# SCH_MAX153_interceptor_2023-04-02.net
KiCad netlist of a schematic drawn in EasyEDA
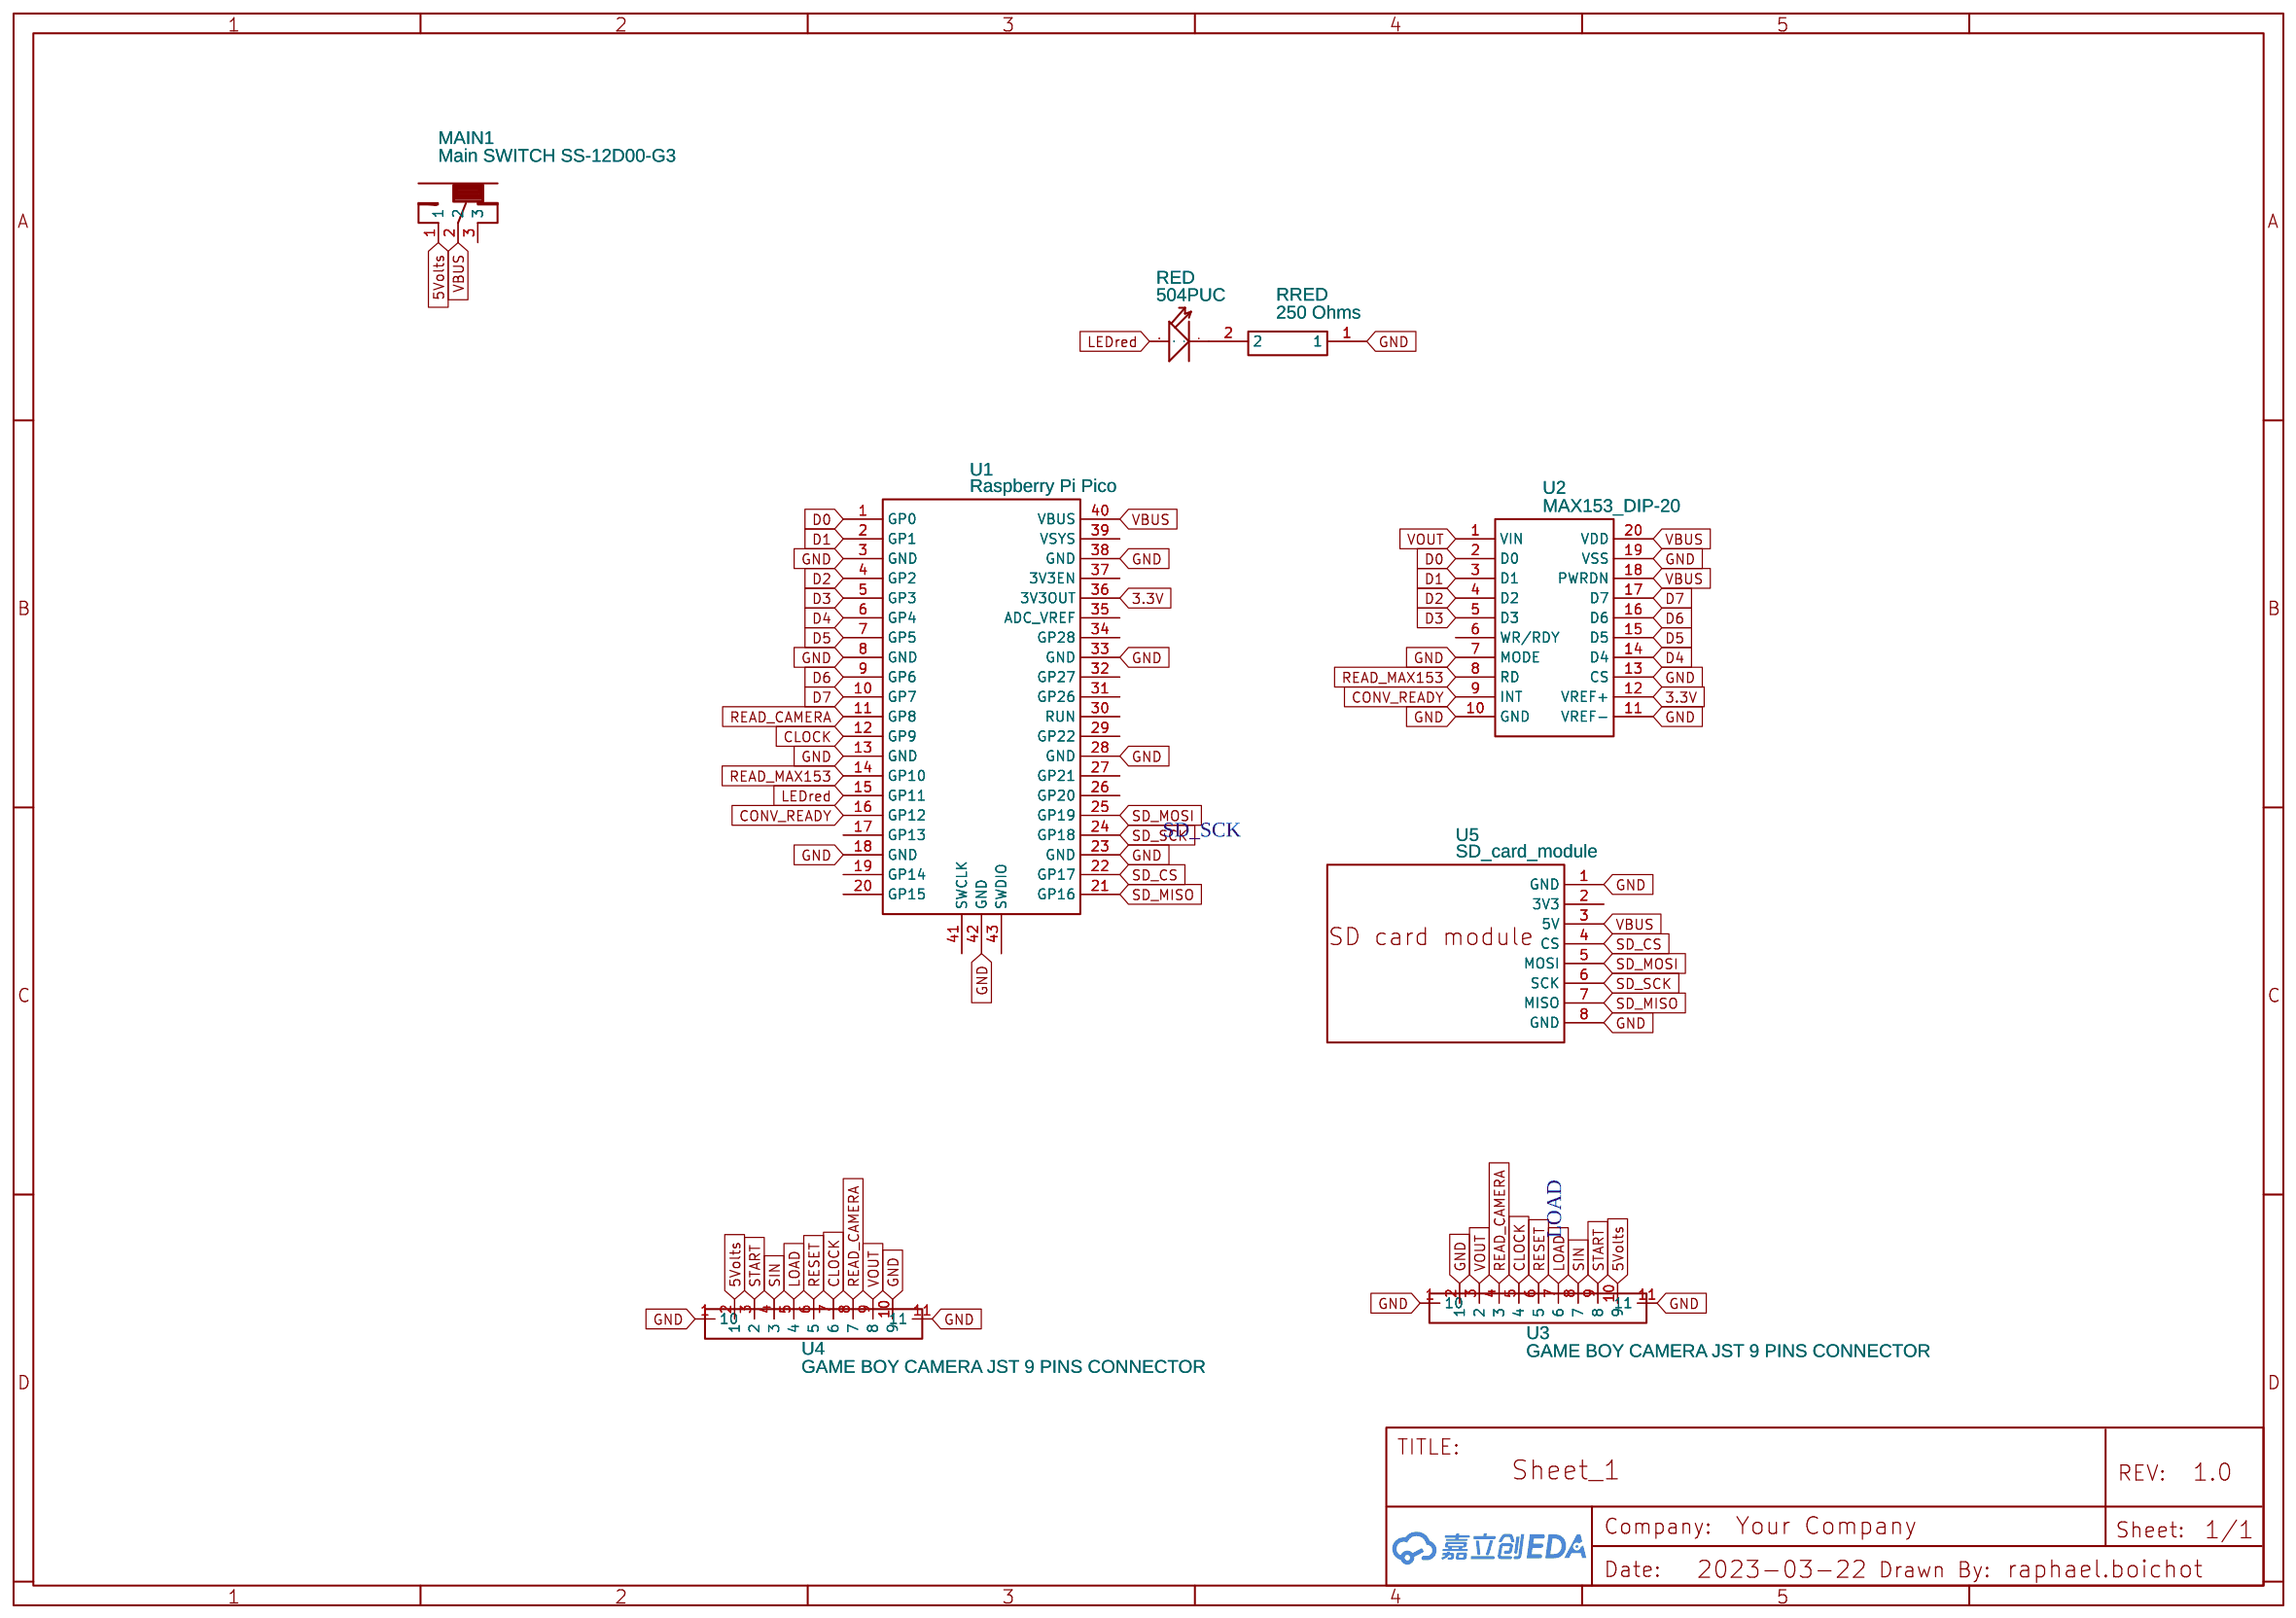
[diagram p0: schematic sheet]

(export (version "E")
  (design (tool "Eeschema 10.0.6"))
  (components
    (comp (ref "MAIN1")
      (value "Main SWITCH SS-12D00-G3")
      (fields (field (name "BOM_Manufacturer Part") "TOGGLE SWITCH SS-12D00-G3"))
      (libsource (lib "") (part "TOGGLE SWITCH SS-12D00-G3"))
    )
    (comp (ref "RED") (value "504PUC") (libsource (lib "") (part "504PUC")))
    (comp (ref "RRED") (value "250 Ohms") (libsource (lib "") (part "RESITOR")))
    (comp (ref "U1") (value "Raspberry Pi Pico") (libsource (lib "") (part "Raspberry Pi Pico")))
    (comp (ref "U2") (value "MAX153_DIP-20") (libsource (lib "") (part "MAX153_DIP-20")))
    (comp (ref "U3")
      (value "GAME BOY CAMERA JST 9 PINS CONNECTOR")
      (libsource (lib "") (part "GAME BOY CAMERA JST 9 PINS CONNECTOR"))
    )
    (comp (ref "U4")
      (value "GAME BOY CAMERA JST 9 PINS CONNECTOR")
      (libsource (lib "") (part "GAME BOY CAMERA JST 9 PINS CONNECTOR_1"))
    )
    (comp (ref "U5") (value "SD_card_module") (libsource (lib "") (part "SD_card_module")))
  )
  (nets
    (net (code "1") (name "3.3V") (class "Default")
      (node (ref "U1") (pin "36") (pinfunction "3V3OUT_36") (pintype "unspecified"))
      (node (ref "U2") (pin "12") (pinfunction "VREF+_12") (pintype "unspecified"))
    )
    (net (code "2") (name "5Volts") (class "Default")
      (node (ref "MAIN1") (pin "1") (pinfunction "1_1") (pintype "bidirectional"))
      (node (ref "U3") (pin "10") (pinfunction "9_10") (pintype "unspecified"))
      (node (ref "U4") (pin "2") (pinfunction "1_2") (pintype "unspecified"))
    )
    (net (code "3") (name "CLOCK") (class "Default")
      (node (ref "U1") (pin "12") (pinfunction "GP9_12") (pintype "unspecified"))
      (node (ref "U3") (pin "5") (pinfunction "4_5") (pintype "unspecified"))
      (node (ref "U4") (pin "7") (pinfunction "6_7") (pintype "unspecified"))
    )
    (net (code "4") (name "CONV_READY") (class "Default")
      (node (ref "U1") (pin "16") (pinfunction "GP12_16") (pintype "unspecified"))
      (node (ref "U2") (pin "9") (pinfunction "INT_9") (pintype "unspecified"))
    )
    (net (code "5") (name "D0") (class "Default")
      (node (ref "U1") (pin "1") (pinfunction "GP0_1") (pintype "unspecified"))
      (node (ref "U2") (pin "2") (pinfunction "D0_2") (pintype "unspecified"))
    )
    (net (code "6") (name "D1") (class "Default")
      (node (ref "U1") (pin "2") (pinfunction "GP1_2") (pintype "unspecified"))
      (node (ref "U2") (pin "3") (pinfunction "D1_3") (pintype "unspecified"))
    )
    (net (code "7") (name "D2") (class "Default")
      (node (ref "U1") (pin "4") (pinfunction "GP2_4") (pintype "unspecified"))
      (node (ref "U2") (pin "4") (pinfunction "D2_4") (pintype "unspecified"))
    )
    (net (code "8") (name "D3") (class "Default")
      (node (ref "U1") (pin "5") (pinfunction "GP3_5") (pintype "unspecified"))
      (node (ref "U2") (pin "5") (pinfunction "D3_5") (pintype "unspecified"))
    )
    (net (code "9") (name "D4") (class "Default")
      (node (ref "U1") (pin "6") (pinfunction "GP4_6") (pintype "unspecified"))
      (node (ref "U2") (pin "14") (pinfunction "D4_14") (pintype "unspecified"))
    )
    (net (code "10") (name "D5") (class "Default")
      (node (ref "U1") (pin "7") (pinfunction "GP5_7") (pintype "unspecified"))
      (node (ref "U2") (pin "15") (pinfunction "D5_15") (pintype "unspecified"))
    )
    (net (code "11") (name "D6") (class "Default")
      (node (ref "U1") (pin "9") (pinfunction "GP6_9") (pintype "unspecified"))
      (node (ref "U2") (pin "16") (pinfunction "D6_16") (pintype "unspecified"))
    )
    (net (code "12") (name "D7") (class "Default")
      (node (ref "U1") (pin "10") (pinfunction "GP7_10") (pintype "unspecified"))
      (node (ref "U2") (pin "17") (pinfunction "D7_17") (pintype "unspecified"))
    )
    (net (code "13") (name "GND") (class "Default")
      (node (ref "RRED") (pin "1") (pinfunction "1_1") (pintype "unspecified"))
      (node (ref "U1") (pin "13") (pinfunction "GND_13") (pintype "unspecified"))
      (node (ref "U1") (pin "18") (pinfunction "GND_18") (pintype "unspecified"))
      (node (ref "U1") (pin "23") (pinfunction "GND_23") (pintype "unspecified"))
      (node (ref "U1") (pin "28") (pinfunction "GND_28") (pintype "unspecified"))
      (node (ref "U1") (pin "3") (pinfunction "GND_3") (pintype "unspecified"))
      (node (ref "U1") (pin "33") (pinfunction "GND_33") (pintype "unspecified"))
      (node (ref "U1") (pin "38") (pinfunction "GND_38") (pintype "unspecified"))
      (node (ref "U1") (pin "42") (pinfunction "GND_42") (pintype "unspecified"))
      (node (ref "U1") (pin "8") (pinfunction "GND_8") (pintype "unspecified"))
      (node (ref "U2") (pin "10") (pinfunction "GND_10") (pintype "unspecified"))
      (node (ref "U2") (pin "11") (pinfunction "VREF-_11") (pintype "unspecified"))
      (node (ref "U2") (pin "13") (pinfunction "CS_13") (pintype "unspecified"))
      (node (ref "U2") (pin "19") (pinfunction "VSS_19") (pintype "unspecified"))
      (node (ref "U2") (pin "7") (pinfunction "MODE_7") (pintype "unspecified"))
      (node (ref "U3") (pin "1") (pinfunction "10_1") (pintype "unspecified"))
      (node (ref "U3") (pin "11") (pinfunction "11_11") (pintype "unspecified"))
      (node (ref "U3") (pin "2") (pinfunction "1_2") (pintype "unspecified"))
      (node (ref "U4") (pin "1") (pinfunction "10_1") (pintype "unspecified"))
      (node (ref "U4") (pin "10") (pinfunction "9_10") (pintype "unspecified"))
      (node (ref "U4") (pin "11") (pinfunction "11_11") (pintype "unspecified"))
      (node (ref "U5") (pin "1") (pinfunction "GND_1") (pintype "unspecified"))
      (node (ref "U5") (pin "8") (pinfunction "GND_8") (pintype "unspecified"))
    )
    (net (code "14") (name "LEDred") (class "Default")
      (node (ref "RED") (pin "+") (pinfunction "+_+") (pintype "unspecified"))
      (node (ref "U1") (pin "15") (pinfunction "GP11_15") (pintype "unspecified"))
    )
    (net (code "15") (name "LOAD") (class "Default")
      (node (ref "U3") (pin "7") (pinfunction "6_7") (pintype "unspecified"))
      (node (ref "U4") (pin "5") (pinfunction "4_5") (pintype "unspecified"))
    )
    (net (code "16") (name "Net-(RED-Pad-)") (class "Default")
      (node (ref "RED") (pin "-") (pinfunction "-_-") (pintype "unspecified"))
      (node (ref "RRED") (pin "2") (pinfunction "2_2") (pintype "unspecified"))
    )
    (net (code "17") (name "READ_CAMERA") (class "Default")
      (node (ref "U1") (pin "11") (pinfunction "GP8_11") (pintype "unspecified"))
      (node (ref "U3") (pin "4") (pinfunction "3_4") (pintype "unspecified"))
      (node (ref "U4") (pin "8") (pinfunction "7_8") (pintype "unspecified"))
    )
    (net (code "18") (name "READ_MAX153") (class "Default")
      (node (ref "U1") (pin "14") (pinfunction "GP10_14") (pintype "unspecified"))
      (node (ref "U2") (pin "8") (pinfunction "RD_8") (pintype "unspecified"))
    )
    (net (code "19") (name "RESET") (class "Default")
      (node (ref "U3") (pin "6") (pinfunction "5_6") (pintype "unspecified"))
      (node (ref "U4") (pin "6") (pinfunction "5_6") (pintype "unspecified"))
    )
    (net (code "20") (name "SD_CS") (class "Default")
      (node (ref "U1") (pin "22") (pinfunction "GP17_22") (pintype "unspecified"))
      (node (ref "U5") (pin "4") (pinfunction "CS_4") (pintype "unspecified"))
    )
    (net (code "21") (name "SD_MISO") (class "Default")
      (node (ref "U1") (pin "21") (pinfunction "GP16_21") (pintype "unspecified"))
      (node (ref "U5") (pin "7") (pinfunction "MISO_7") (pintype "unspecified"))
    )
    (net (code "22") (name "SD_MOSI") (class "Default")
      (node (ref "U1") (pin "25") (pinfunction "GP19_25") (pintype "unspecified"))
      (node (ref "U5") (pin "5") (pinfunction "MOSI_5") (pintype "unspecified"))
    )
    (net (code "23") (name "SD_SCK") (class "Default")
      (node (ref "U1") (pin "24") (pinfunction "GP18_24") (pintype "unspecified"))
      (node (ref "U5") (pin "6") (pinfunction "SCK_6") (pintype "unspecified"))
    )
    (net (code "24") (name "SIN") (class "Default")
      (node (ref "U3") (pin "8") (pinfunction "7_8") (pintype "unspecified"))
      (node (ref "U4") (pin "4") (pinfunction "3_4") (pintype "unspecified"))
    )
    (net (code "25") (name "START") (class "Default")
      (node (ref "U3") (pin "9") (pinfunction "8_9") (pintype "unspecified"))
      (node (ref "U4") (pin "3") (pinfunction "2_3") (pintype "unspecified"))
    )
    (net (code "26") (name "VBUS") (class "Default")
      (node (ref "MAIN1") (pin "2") (pinfunction "2_2") (pintype "bidirectional"))
      (node (ref "U1") (pin "40") (pinfunction "VBUS_40") (pintype "unspecified"))
      (node (ref "U2") (pin "18") (pinfunction "PWRDN_18") (pintype "unspecified"))
      (node (ref "U2") (pin "20") (pinfunction "VDD_20") (pintype "unspecified"))
      (node (ref "U5") (pin "3") (pinfunction "5V_3") (pintype "unspecified"))
    )
    (net (code "27") (name "VOUT") (class "Default")
      (node (ref "U2") (pin "1") (pinfunction "VIN_1") (pintype "unspecified"))
      (node (ref "U3") (pin "3") (pinfunction "2_3") (pintype "unspecified"))
      (node (ref "U4") (pin "9") (pinfunction "8_9") (pintype "unspecified"))
    )
    (net (code "28") (name "unconnected-(MAIN1-Pad3)") (class "Default")
      (node (ref "MAIN1") (pin "3") (pinfunction "3_3") (pintype "unspecified"))
    )
    (net (code "29") (name "unconnected-(U1-3V3EN-Pad37)") (class "Default")
      (node (ref "U1") (pin "37") (pinfunction "3V3EN_37") (pintype "unspecified"))
    )
    (net (code "30") (name "unconnected-(U1-ADC_VREF-Pad35)") (class "Default")
      (node (ref "U1") (pin "35") (pinfunction "ADC_VREF_35") (pintype "unspecified"))
    )
    (net (code "31") (name "unconnected-(U1-GP13-Pad17)") (class "Default")
      (node (ref "U1") (pin "17") (pinfunction "GP13_17") (pintype "unspecified"))
    )
    (net (code "32") (name "unconnected-(U1-GP14-Pad19)") (class "Default")
      (node (ref "U1") (pin "19") (pinfunction "GP14_19") (pintype "unspecified"))
    )
    (net (code "33") (name "unconnected-(U1-GP15-Pad20)") (class "Default")
      (node (ref "U1") (pin "20") (pinfunction "GP15_20") (pintype "unspecified"))
    )
    (net (code "34") (name "unconnected-(U1-GP20-Pad26)") (class "Default")
      (node (ref "U1") (pin "26") (pinfunction "GP20_26") (pintype "unspecified"))
    )
    (net (code "35") (name "unconnected-(U1-GP21-Pad27)") (class "Default")
      (node (ref "U1") (pin "27") (pinfunction "GP21_27") (pintype "unspecified"))
    )
    (net (code "36") (name "unconnected-(U1-GP22-Pad29)") (class "Default")
      (node (ref "U1") (pin "29") (pinfunction "GP22_29") (pintype "unspecified"))
    )
    (net (code "37") (name "unconnected-(U1-GP26-Pad31)") (class "Default")
      (node (ref "U1") (pin "31") (pinfunction "GP26_31") (pintype "unspecified"))
    )
    (net (code "38") (name "unconnected-(U1-GP27-Pad32)") (class "Default")
      (node (ref "U1") (pin "32") (pinfunction "GP27_32") (pintype "unspecified"))
    )
    (net (code "39") (name "unconnected-(U1-GP28-Pad34)") (class "Default")
      (node (ref "U1") (pin "34") (pinfunction "GP28_34") (pintype "unspecified"))
    )
    (net (code "40") (name "unconnected-(U1-RUN-Pad30)") (class "Default")
      (node (ref "U1") (pin "30") (pinfunction "RUN_30") (pintype "unspecified"))
    )
    (net (code "41") (name "unconnected-(U1-SWCLK-Pad41)") (class "Default")
      (node (ref "U1") (pin "41") (pinfunction "SWCLK_41") (pintype "unspecified"))
    )
    (net (code "42") (name "unconnected-(U1-SWDIO-Pad43)") (class "Default")
      (node (ref "U1") (pin "43") (pinfunction "SWDIO_43") (pintype "unspecified"))
    )
    (net (code "43") (name "unconnected-(U1-VSYS-Pad39)") (class "Default")
      (node (ref "U1") (pin "39") (pinfunction "VSYS_39") (pintype "unspecified"))
    )
    (net (code "44") (name "unconnected-(U2-WR{slash}RDY-Pad6)") (class "Default")
      (node (ref "U2") (pin "6") (pinfunction "WR/RDY_6") (pintype "unspecified"))
    )
    (net (code "45") (name "unconnected-(U5-3V3-Pad2)") (class "Default")
      (node (ref "U5") (pin "2") (pinfunction "3V3_2") (pintype "unspecified"))
    )
  )
)
